# Barridotemp.net
KiCad netlist of a schematic drawn in Altium Designer
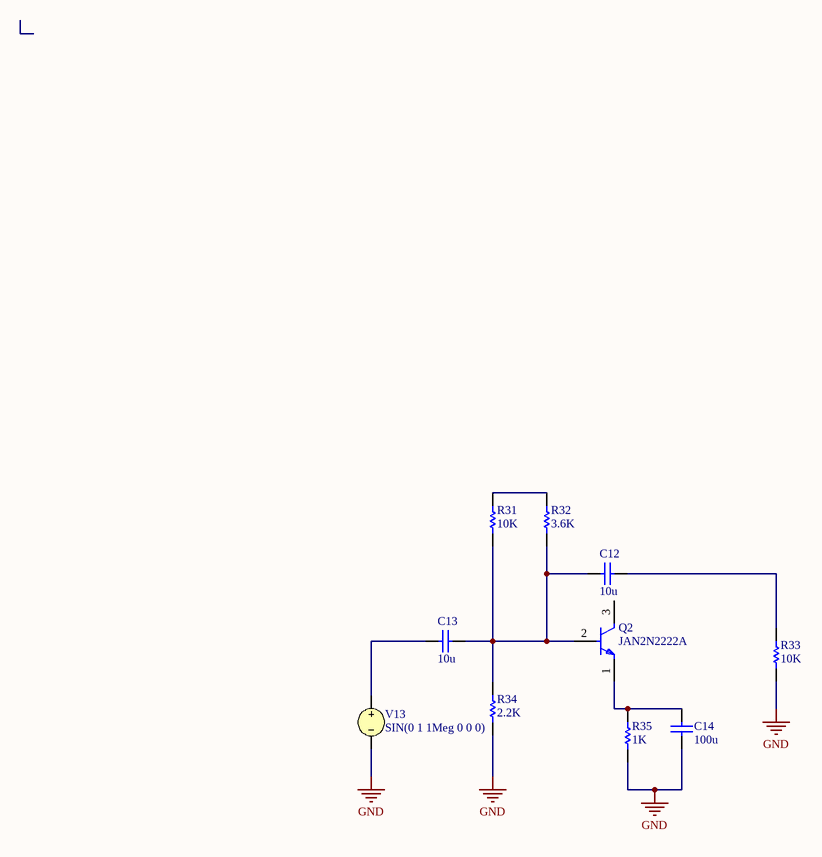
[diagram p0: Barridotemp.SchDoc]

(export (version "E")
  (design (tool "Eeschema 10.0.6"))
  (components
    (comp (ref "C12")
      (value "10u")
      (description "Capacitor")
      (libsource (lib "Simulation Generic Components") (part "Capacitor"))
    )
    (comp (ref "C13")
      (value "10u")
      (description "Capacitor")
      (libsource (lib "Simulation Generic Components") (part "Capacitor"))
    )
    (comp (ref "C14")
      (value "100u")
      (description "Capacitor")
      (libsource (lib "Simulation Generic Components") (part "Capacitor"))
    )
    (comp (ref "Q2")
      (value "JAN2N2222A")
      (footprint "FP-JAN2N2222A-MFG")
      (description "TRANS NPN 50V 0.8A TO218")
      (libsource (lib "Altium Content Vault") (part "acac84805612edcd38d576ce092733c"))
    )
    (comp (ref "R31")
      (value "10K")
      (description "Resistor")
      (libsource (lib "Simulation Generic Components") (part "Resistor"))
    )
    (comp (ref "R32")
      (value "3.6K")
      (description "Resistor")
      (libsource (lib "Simulation Generic Components") (part "Resistor"))
    )
    (comp (ref "R33")
      (value "10K")
      (description "Resistor")
      (libsource (lib "Simulation Generic Components") (part "Resistor"))
    )
    (comp (ref "R34")
      (value "2.2K")
      (description "Resistor")
      (libsource (lib "Simulation Generic Components") (part "Resistor"))
    )
    (comp (ref "R35")
      (value "1K")
      (description "Resistor")
      (libsource (lib "Simulation Generic Components") (part "Resistor"))
    )
    (comp (ref "V13")
      (value "SIN(0 1 1Meg 0 0 0)")
      (description "Voltage Source")
      (fields (field (name "PUBLISHER") "Altium Limited"))
      (libsource (lib "Simulation Generic Components") (part "VSRC"))
    )
  )
  (nets
    (net (code "1") (name "GND") (class "Default")
      (node (ref "C14") (pin "1") (pinfunction "1_1") (pintype "passive"))
      (node (ref "R33") (pin "1") (pinfunction "1_1") (pintype "passive"))
      (node (ref "R34") (pin "1") (pinfunction "1_1") (pintype "passive"))
      (node (ref "R35") (pin "1") (pinfunction "1_1") (pintype "passive"))
      (node (ref "V13") (pin "2") (pinfunction "2_2") (pintype "passive"))
    )
    (net (code "2") (name "Net-(C12-Pad2)") (class "Default")
      (node (ref "C12") (pin "2") (pinfunction "2_2") (pintype "passive"))
      (node (ref "R33") (pin "2") (pinfunction "2_2") (pintype "passive"))
    )
    (net (code "3") (name "Net-(C13-Pad1)") (class "Default")
      (node (ref "C13") (pin "1") (pinfunction "1_1") (pintype "passive"))
      (node (ref "V13") (pin "1") (pinfunction "1_1") (pintype "passive"))
    )
    (net (code "4") (name "Net-(Q2-B)") (class "Default")
      (node (ref "C12") (pin "1") (pinfunction "1_1") (pintype "passive"))
      (node (ref "C13") (pin "2") (pinfunction "2_2") (pintype "passive"))
      (node (ref "Q2") (pin "2") (pinfunction "B_2") (pintype "passive"))
      (node (ref "R31") (pin "1") (pinfunction "1_1") (pintype "passive"))
      (node (ref "R32") (pin "1") (pinfunction "1_1") (pintype "passive"))
      (node (ref "R34") (pin "2") (pinfunction "2_2") (pintype "passive"))
    )
    (net (code "5") (name "Net-(Q2-E)") (class "Default")
      (node (ref "C14") (pin "2") (pinfunction "2_2") (pintype "passive"))
      (node (ref "Q2") (pin "1") (pinfunction "E_1") (pintype "passive"))
      (node (ref "R35") (pin "2") (pinfunction "2_2") (pintype "passive"))
    )
    (net (code "6") (name "Net-(R31-Pad2)") (class "Default")
      (node (ref "R31") (pin "2") (pinfunction "2_2") (pintype "passive"))
      (node (ref "R32") (pin "2") (pinfunction "2_2") (pintype "passive"))
    )
    (net (code "7") (name "unconnected-(Q2-C-Pad3)") (class "Default")
      (node (ref "Q2") (pin "3") (pinfunction "C_3") (pintype "passive"))
    )
  )
)
